# TPS62237_Breakout.net
KiCad netlist of a schematic drawn in EAGLE
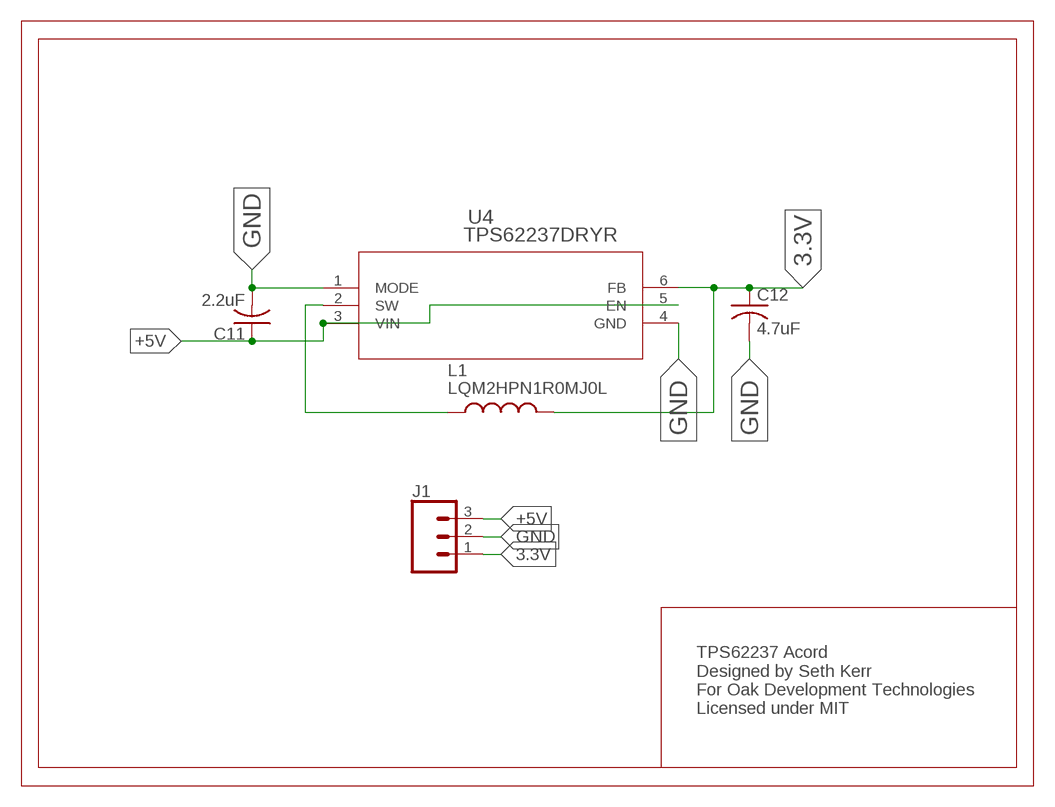
[diagram p0: schematic, sheet 1]

(export (version "E")
  (design (tool "Eeschema 10.0.6"))
  (components
    (comp (ref "C11")
      (value "2.2uF")
      (footprint "eagle-import:C0603")
      (libsource (lib "eagle-import") (part "C-USC0603"))
    )
    (comp (ref "C12")
      (value "4.7uF")
      (footprint "eagle-import:C0603")
      (libsource (lib "eagle-import") (part "C-USC0603"))
    )
    (comp (ref "J1")
      (value "CONN_031X03_NO_SILK")
      (footprint "eagle-import:1X03_NO_SILK")
      (libsource (lib "eagle-import") (part "CONN_031X03_NO_SILK"))
    )
    (comp (ref "L1")
      (value "LQM2HPN1R0MJ0L")
      (footprint "eagle-import:INDC2520X120N")
      (fields (field (name "DIGI-KEY_PART_NUMBER") "490-6699-1-ND") (field (name "MF") "Murata Electronics"))
      (libsource (lib "eagle-import") (part "LQM2HPN1R0MJ0L"))
    )
    (comp (ref "U4")
      (value "TPS62237DRYR")
      (footprint "eagle-import:DRY6_TEX")
      (fields (field (name "MANUFACTURER") "Texas Instruments"))
      (libsource (lib "eagle-import") (part "TPS62237DRYR"))
    )
  )
  (nets
    (net (code "1") (name "+5V") (class "Default")
      (node (ref "C11") (pin "1") (pinfunction "1_1") (pintype "passive"))
      (node (ref "J1") (pin "3") (pinfunction "3_3") (pintype "passive"))
      (node (ref "U4") (pin "3") (pinfunction "VIN_3") (pintype "power_in"))
      (node (ref "U4") (pin "5") (pinfunction "EN_5") (pintype "input"))
    )
    (net (code "2") (name "3.3V") (class "Default")
      (node (ref "C12") (pin "1") (pinfunction "1_1") (pintype "passive"))
      (node (ref "J1") (pin "1") (pinfunction "1_1") (pintype "passive"))
      (node (ref "L1") (pin "2") (pinfunction "2_2") (pintype "passive"))
      (node (ref "U4") (pin "6") (pinfunction "FB_6") (pintype "input"))
    )
    (net (code "3") (name "GND") (class "Default")
      (node (ref "C11") (pin "2") (pinfunction "2_2") (pintype "passive"))
      (node (ref "C12") (pin "2") (pinfunction "2_2") (pintype "passive"))
      (node (ref "J1") (pin "2") (pinfunction "2_2") (pintype "passive"))
      (node (ref "U4") (pin "1") (pinfunction "MODE_1") (pintype "input"))
      (node (ref "U4") (pin "4") (pinfunction "GND_4") (pintype "power_in"))
    )
    (net (code "4") (name "Net-(U4-SW)") (class "Default")
      (node (ref "L1") (pin "1") (pinfunction "1_1") (pintype "passive"))
      (node (ref "U4") (pin "2") (pinfunction "SW_2") (pintype "output"))
    )
  )
)
